# USBBoost.net
KiCad netlist of a schematic drawn in EAGLE
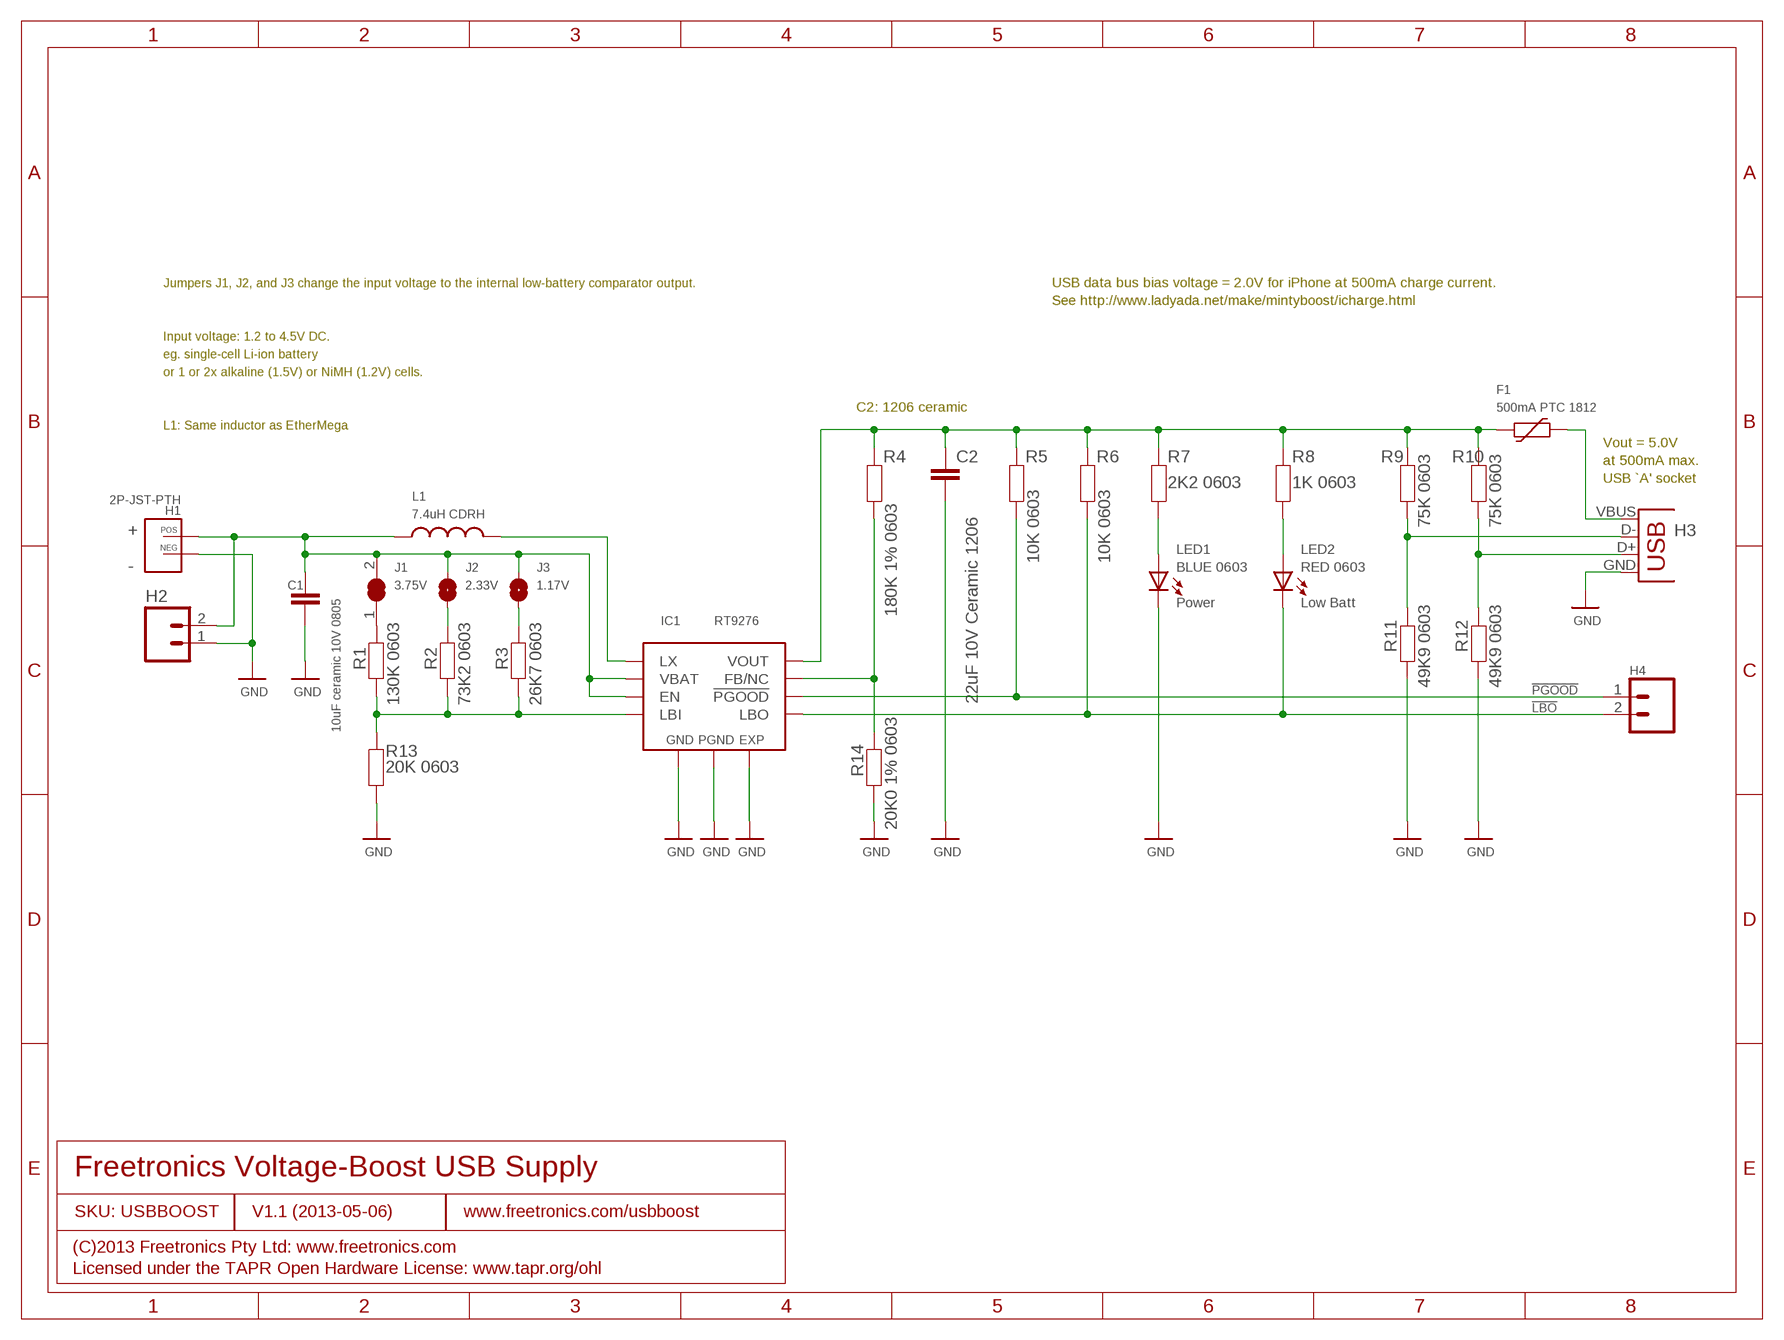
[diagram p0: schematic, sheet 1]

(export (version "E")
  (design (tool "Eeschema 10.0.6"))
  (components
    (comp (ref "C1")
      (value "10uF ceramic 10V 0805")
      (footprint "eagle-import:C0805")
      (libsource (lib "eagle-import") (part "C-EUC0805"))
    )
    (comp (ref "C2")
      (value "22uF 10V Ceramic 1206")
      (footprint "eagle-import:C1206K")
      (libsource (lib "eagle-import") (part "C-EUC1206K"))
    )
    (comp (ref "F1")
      (value "500mA PTC 1812")
      (footprint "eagle-import:1812")
      (libsource (lib "eagle-import") (part "PTC"))
    )
    (comp (ref "H1")
      (value "2P-JST-PTH")
      (footprint "eagle-import:JST-2MM-TH-RA")
      (libsource (lib "eagle-import") (part "2P-JST-TH-RAPTH"))
    )
    (comp (ref "H2")
      (value "M02PTH")
      (footprint "eagle-import:1X02")
      (libsource (lib "eagle-import") (part "freetronics-master-v1.1_M02PTH"))
    )
    (comp (ref "H3")
      (value "USB")
      (footprint "eagle-import:USB-A-S-SILK-FEMALE")
      (libsource (lib "eagle-import") (part "USB_"))
    )
    (comp (ref "H4")
      (value "Status")
      (footprint "eagle-import:1X02")
      (libsource (lib "eagle-import") (part "M02PTH"))
    )
    (comp (ref "IC1")
      (value "RT9276")
      (footprint "eagle-import:WDFN-10L-3X3")
      (libsource (lib "eagle-import") (part "RT9276"))
    )
    (comp (ref "J1")
      (value "3.75V")
      (footprint "eagle-import:SJC")
      (libsource (lib "eagle-import") (part "SJCN"))
    )
    (comp (ref "J2")
      (value "2.33V")
      (footprint "eagle-import:SJ")
      (libsource (lib "eagle-import") (part "SJ"))
    )
    (comp (ref "J3")
      (value "1.17V")
      (footprint "eagle-import:SJ")
      (libsource (lib "eagle-import") (part "SJ"))
    )
    (comp (ref "L1")
      (value "7.4uH CDRH")
      (footprint "eagle-import:CDRH")
      (libsource (lib "eagle-import") (part "INDUCTOR"))
    )
    (comp (ref "LED1")
      (value "BLUE 0603")
      (footprint "eagle-import:LED-0603")
      (libsource (lib "eagle-import") (part "LED0603"))
    )
    (comp (ref "LED2")
      (value "RED 0603")
      (footprint "eagle-import:LED-0603")
      (libsource (lib "eagle-import") (part "LED0603"))
    )
    (comp (ref "R1")
      (value "130K 0603")
      (footprint "eagle-import:0603")
      (libsource (lib "eagle-import") (part "RESISTOR0603"))
    )
    (comp (ref "R2")
      (value "73K2 0603")
      (footprint "eagle-import:0603")
      (libsource (lib "eagle-import") (part "freetronics-original_RESISTOR0603"))
    )
    (comp (ref "R3")
      (value "26K7 0603")
      (footprint "eagle-import:0603")
      (libsource (lib "eagle-import") (part "freetronics-original_RESISTOR0603"))
    )
    (comp (ref "R4")
      (value "180K 1% 0603")
      (footprint "eagle-import:0603")
      (libsource (lib "eagle-import") (part "freetronics-original_RESISTOR0603"))
    )
    (comp (ref "R5")
      (value "10K 0603")
      (footprint "eagle-import:0603")
      (libsource (lib "eagle-import") (part "freetronics-original_RESISTOR0603"))
    )
    (comp (ref "R6")
      (value "10K 0603")
      (footprint "eagle-import:0603")
      (libsource (lib "eagle-import") (part "freetronics-original_RESISTOR0603"))
    )
    (comp (ref "R7")
      (value "2K2 0603")
      (footprint "eagle-import:0603")
      (libsource (lib "eagle-import") (part "freetronics-original_RESISTOR0603"))
    )
    (comp (ref "R8")
      (value "1K 0603")
      (footprint "eagle-import:0603")
      (libsource (lib "eagle-import") (part "freetronics-original_RESISTOR0603"))
    )
    (comp (ref "R9")
      (value "75K 0603")
      (footprint "eagle-import:0603")
      (libsource (lib "eagle-import") (part "freetronics-original_RESISTOR0603"))
    )
    (comp (ref "R10")
      (value "75K 0603")
      (footprint "eagle-import:0603")
      (libsource (lib "eagle-import") (part "freetronics-original_RESISTOR0603"))
    )
    (comp (ref "R11")
      (value "49K9 0603")
      (footprint "eagle-import:0603")
      (libsource (lib "eagle-import") (part "freetronics-original_RESISTOR0603"))
    )
    (comp (ref "R12")
      (value "49K9 0603")
      (footprint "eagle-import:0603")
      (libsource (lib "eagle-import") (part "freetronics-original_RESISTOR0603"))
    )
    (comp (ref "R13")
      (value "20K 0603")
      (footprint "eagle-import:0603")
      (libsource (lib "eagle-import") (part "freetronics-original_RESISTOR0603"))
    )
    (comp (ref "R14")
      (value "20K0 1% 0603")
      (footprint "eagle-import:0603")
      (libsource (lib "eagle-import") (part "freetronics-original_RESISTOR0603"))
    )
  )
  (nets
    (net (code "1") (name "/~{LBO}") (class "Default")
      (node (ref "H4") (pin "2") (pinfunction "2_2") (pintype "passive"))
      (node (ref "IC1") (pin "4") (pinfunction "LBO_4") (pintype "passive"))
      (node (ref "LED2") (pin "C") (pinfunction "C_C") (pintype "passive"))
      (node (ref "R6") (pin "2") (pinfunction "2_2") (pintype "passive"))
    )
    (net (code "2") (name "/~{PGOOD}") (class "Default")
      (node (ref "H4") (pin "1") (pinfunction "1_1") (pintype "passive"))
      (node (ref "IC1") (pin "8") (pinfunction "~{PGOOD}_8") (pintype "passive"))
      (node (ref "R5") (pin "2") (pinfunction "2_2") (pintype "passive"))
    )
    (net (code "3") (name "GND") (class "Default")
      (node (ref "C1") (pin "2") (pinfunction "2_2") (pintype "passive"))
      (node (ref "C2") (pin "2") (pinfunction "2_2") (pintype "passive"))
      (node (ref "H1") (pin "NEG") (pinfunction "NEG_NEG") (pintype "power_in"))
      (node (ref "H2") (pin "1") (pinfunction "1_1") (pintype "passive"))
      (node (ref "H3") (pin "GND") (pinfunction "GND_GND") (pintype "bidirectional"))
      (node (ref "IC1") (pin "10") (pinfunction "PGND_10") (pintype "power_in"))
      (node (ref "IC1") (pin "5") (pinfunction "GND_5") (pintype "power_in"))
      (node (ref "IC1") (pin "EXP") (pinfunction "EXP_EXP") (pintype "power_in"))
      (node (ref "LED1") (pin "C") (pinfunction "C_C") (pintype "passive"))
      (node (ref "R11") (pin "2") (pinfunction "2_2") (pintype "passive"))
      (node (ref "R12") (pin "2") (pinfunction "2_2") (pintype "passive"))
      (node (ref "R13") (pin "1") (pinfunction "1_1") (pintype "passive"))
      (node (ref "R14") (pin "1") (pinfunction "1_1") (pintype "passive"))
    )
    (net (code "4") (name "Net-(F1-P$1)") (class "Default")
      (node (ref "C2") (pin "1") (pinfunction "1_1") (pintype "passive"))
      (node (ref "F1") (pin "1") (pinfunction "P$1_1") (pintype "bidirectional"))
      (node (ref "IC1") (pin "2") (pinfunction "VOUT_2") (pintype "passive"))
      (node (ref "R10") (pin "1") (pinfunction "1_1") (pintype "passive"))
      (node (ref "R4") (pin "1") (pinfunction "1_1") (pintype "passive"))
      (node (ref "R5") (pin "1") (pinfunction "1_1") (pintype "passive"))
      (node (ref "R6") (pin "1") (pinfunction "1_1") (pintype "passive"))
      (node (ref "R7") (pin "1") (pinfunction "1_1") (pintype "passive"))
      (node (ref "R8") (pin "1") (pinfunction "1_1") (pintype "passive"))
      (node (ref "R9") (pin "1") (pinfunction "1_1") (pintype "passive"))
    )
    (net (code "5") (name "Net-(F1-P$2)") (class "Default")
      (node (ref "F1") (pin "2") (pinfunction "P$2_2") (pintype "bidirectional"))
      (node (ref "H3") (pin "VBUS") (pinfunction "VBUS_VBUS") (pintype "bidirectional"))
    )
    (net (code "6") (name "Net-(H3-PadD+)") (class "Default")
      (node (ref "H3") (pin "D+") (pinfunction "D+_D+") (pintype "bidirectional"))
      (node (ref "R10") (pin "2") (pinfunction "2_2") (pintype "passive"))
      (node (ref "R12") (pin "1") (pinfunction "1_1") (pintype "passive"))
    )
    (net (code "7") (name "Net-(H3-PadD-)") (class "Default")
      (node (ref "H3") (pin "D-") (pinfunction "D-_D-") (pintype "bidirectional"))
      (node (ref "R11") (pin "1") (pinfunction "1_1") (pintype "passive"))
      (node (ref "R9") (pin "2") (pinfunction "2_2") (pintype "passive"))
    )
    (net (code "8") (name "Net-(IC1-EN)") (class "Default")
      (node (ref "C1") (pin "1") (pinfunction "1_1") (pintype "passive"))
      (node (ref "H1") (pin "POS") (pinfunction "POS_POS") (pintype "power_in"))
      (node (ref "H2") (pin "2") (pinfunction "2_2") (pintype "passive"))
      (node (ref "IC1") (pin "1") (pinfunction "EN_1") (pintype "passive"))
      (node (ref "IC1") (pin "6") (pinfunction "VBAT_6") (pintype "passive"))
      (node (ref "J1") (pin "2") (pinfunction "2_2") (pintype "passive"))
      (node (ref "J2") (pin "2") (pinfunction "2_2") (pintype "passive"))
      (node (ref "J3") (pin "2") (pinfunction "2_2") (pintype "passive"))
      (node (ref "L1") (pin "1") (pinfunction "1_1") (pintype "bidirectional"))
    )
    (net (code "9") (name "Net-(IC1-FB{slash}NC)") (class "Default")
      (node (ref "IC1") (pin "3") (pinfunction "FB/NC_3") (pintype "passive"))
      (node (ref "R14") (pin "2") (pinfunction "2_2") (pintype "passive"))
      (node (ref "R4") (pin "2") (pinfunction "2_2") (pintype "passive"))
    )
    (net (code "10") (name "Net-(IC1-LBI)") (class "Default")
      (node (ref "IC1") (pin "7") (pinfunction "LBI_7") (pintype "passive"))
      (node (ref "R1") (pin "1") (pinfunction "1_1") (pintype "passive"))
      (node (ref "R13") (pin "2") (pinfunction "2_2") (pintype "passive"))
      (node (ref "R2") (pin "1") (pinfunction "1_1") (pintype "passive"))
      (node (ref "R3") (pin "1") (pinfunction "1_1") (pintype "passive"))
    )
    (net (code "11") (name "Net-(IC1-LX)") (class "Default")
      (node (ref "IC1") (pin "9") (pinfunction "LX_9") (pintype "passive"))
      (node (ref "L1") (pin "2") (pinfunction "2_2") (pintype "bidirectional"))
    )
    (net (code "12") (name "Net-(J1-Pad1)") (class "Default")
      (node (ref "J1") (pin "1") (pinfunction "1_1") (pintype "passive"))
      (node (ref "R1") (pin "2") (pinfunction "2_2") (pintype "passive"))
    )
    (net (code "13") (name "Net-(J2-Pad1)") (class "Default")
      (node (ref "J2") (pin "1") (pinfunction "1_1") (pintype "passive"))
      (node (ref "R2") (pin "2") (pinfunction "2_2") (pintype "passive"))
    )
    (net (code "14") (name "Net-(J3-Pad1)") (class "Default")
      (node (ref "J3") (pin "1") (pinfunction "1_1") (pintype "passive"))
      (node (ref "R3") (pin "2") (pinfunction "2_2") (pintype "passive"))
    )
    (net (code "15") (name "Net-(LED1-PadA)") (class "Default")
      (node (ref "LED1") (pin "A") (pinfunction "A_A") (pintype "passive"))
      (node (ref "R7") (pin "2") (pinfunction "2_2") (pintype "passive"))
    )
    (net (code "16") (name "Net-(LED2-PadA)") (class "Default")
      (node (ref "LED2") (pin "A") (pinfunction "A_A") (pintype "passive"))
      (node (ref "R8") (pin "2") (pinfunction "2_2") (pintype "passive"))
    )
  )
)
